# campainha.net
KiCad netlist of a schematic drawn in EAGLE
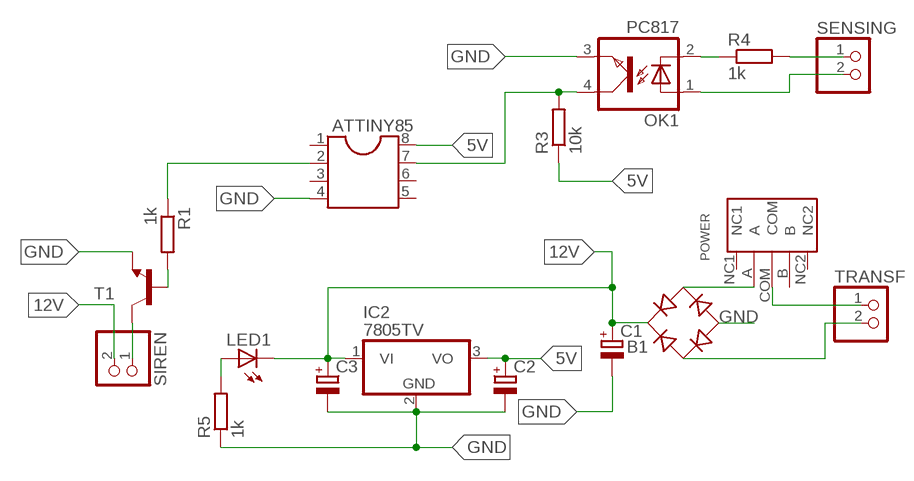
[diagram p0: schematic, sheet 1]

(export (version "E")
  (design (tool "Eeschema 10.0.6"))
  (components
    (comp (ref "ATTINY85")
      (value "DIL8S")
      (footprint "eagle-import:SOCKET-08")
      (libsource (lib "eagle-import") (part "DIL8S"))
    )
    (comp (ref "B1")
      (value "DBDB104G")
      (footprint "eagle-import:DB")
      (libsource (lib "eagle-import") (part "DB?GDB104"))
    )
    (comp (ref "C1")
      (value "CPOL-EUE2,5-6E")
      (footprint "eagle-import:E2,5-6E")
      (libsource (lib "eagle-import") (part "CPOL-EUE2,5-6E"))
    )
    (comp (ref "C2")
      (value "CPOL-EUE1.8-4")
      (footprint "eagle-import:E1,8-4")
      (libsource (lib "eagle-import") (part "CPOL-EUE1.8-4"))
    )
    (comp (ref "C3")
      (value "CPOL-EUE1.8-4")
      (footprint "eagle-import:E1,8-4")
      (libsource (lib "eagle-import") (part "CPOL-EUE1.8-4"))
    )
    (comp (ref "IC2")
      (value "7805TV")
      (footprint "eagle-import:TO220V")
      (libsource (lib "eagle-import") (part "78TV05"))
    )
    (comp (ref "LED1")
      (value "LED3MM")
      (footprint "eagle-import:LED3MM")
      (libsource (lib "eagle-import") (part "LED3MM"))
    )
    (comp (ref "OK1")
      (value "PC817")
      (footprint "eagle-import:DIL04")
      (fields (field (name "MPN") "PC817X4J000F"))
      (libsource (lib "eagle-import") (part "PC817"))
    )
    (comp (ref "POWER")
      (value "SWITCH-2H-3P-REINFORCE")
      (footprint "eagle-import:3P-2CH-2.0-8.8X4.4X4.7H-90D-REINFORCE")
      (libsource (lib "eagle-import") (part "SWITCH-2H-3P-REINFORCE"))
    )
    (comp (ref "R1")
      (value "1k")
      (footprint "eagle-import:0204_7")
      (libsource (lib "eagle-import") (part "R-EU_0204/7"))
    )
    (comp (ref "R3")
      (value "10k")
      (footprint "eagle-import:0204_7")
      (libsource (lib "eagle-import") (part "R-EU_0204/7"))
    )
    (comp (ref "R4")
      (value "1k")
      (footprint "eagle-import:0204_7")
      (libsource (lib "eagle-import") (part "R-EU_0204/7"))
    )
    (comp (ref "R5")
      (value "1k")
      (footprint "eagle-import:0204_7")
      (libsource (lib "eagle-import") (part "R-EU_0204/7"))
    )
    (comp (ref "SENSING")
      (value "PINHD-1X2")
      (footprint "eagle-import:1X02")
      (libsource (lib "eagle-import") (part "PINHD-1X2"))
    )
    (comp (ref "SIREN")
      (value "PINHD-1X2")
      (footprint "eagle-import:1X02")
      (libsource (lib "eagle-import") (part "PINHD-1X2"))
    )
    (comp (ref "T1")
      (value "TRANSISTOR_NPNTO92")
      (footprint "eagle-import:TO-92")
      (libsource (lib "eagle-import") (part "TRANSISTOR_NPNTO92"))
    )
    (comp (ref "TRANSF")
      (value "PINHD-1X2")
      (footprint "eagle-import:1X02")
      (libsource (lib "eagle-import") (part "PINHD-1X2"))
    )
  )
  (nets
    (net (code "1") (name "5V") (class "Default")
      (node (ref "ATTINY85") (pin "8") (pinfunction "8_8") (pintype "passive"))
      (node (ref "C2") (pin "+") (pinfunction "+_+") (pintype "passive"))
      (node (ref "IC2") (pin "3") (pinfunction "VO_3") (pintype "passive"))
      (node (ref "R3") (pin "1") (pinfunction "1_1") (pintype "passive"))
    )
    (net (code "2") (name "12V") (class "Default")
      (node (ref "B1") (pin "+") (pinfunction "+_+") (pintype "passive"))
      (node (ref "C1") (pin "+") (pinfunction "+_+") (pintype "passive"))
      (node (ref "C3") (pin "+") (pinfunction "+_+") (pintype "passive"))
      (node (ref "IC2") (pin "1") (pinfunction "VI_1") (pintype "input"))
      (node (ref "LED1") (pin "K") (pinfunction "C_K") (pintype "passive"))
      (node (ref "SIREN") (pin "2") (pinfunction "2_2") (pintype "passive"))
    )
    (net (code "3") (name "GND") (class "Default")
      (node (ref "ATTINY85") (pin "4") (pinfunction "4_4") (pintype "passive"))
      (node (ref "B1") (pin "-") (pinfunction "-_-") (pintype "passive"))
      (node (ref "C1") (pin "-") (pinfunction "-_-") (pintype "passive"))
      (node (ref "C2") (pin "-") (pinfunction "-_-") (pintype "passive"))
      (node (ref "C3") (pin "-") (pinfunction "-_-") (pintype "passive"))
      (node (ref "IC2") (pin "2") (pinfunction "GND_2") (pintype "passive"))
      (node (ref "OK1") (pin "3") (pinfunction "EMIT_3") (pintype "passive"))
      (node (ref "R5") (pin "1") (pinfunction "1_1") (pintype "passive"))
      (node (ref "T1") (pin "1") (pinfunction "E_1") (pintype "passive"))
    )
    (net (code "4") (name "Net-(ATTINY85-Pad2)") (class "Default")
      (node (ref "ATTINY85") (pin "2") (pinfunction "2_2") (pintype "passive"))
      (node (ref "R1") (pin "1") (pinfunction "1_1") (pintype "passive"))
    )
    (net (code "5") (name "Net-(B1-PadAC1)") (class "Default")
      (node (ref "B1") (pin "AC1") (pinfunction "AC1_AC1") (pintype "passive"))
      (node (ref "TRANSF") (pin "2") (pinfunction "2_2") (pintype "passive"))
    )
    (net (code "6") (name "Net-(B1-PadAC2)") (class "Default")
      (node (ref "B1") (pin "AC2") (pinfunction "AC2_AC2") (pintype "passive"))
      (node (ref "POWER") (pin "A") (pinfunction "A_A") (pintype "bidirectional"))
    )
    (net (code "7") (name "Net-(LED1-PadA)") (class "Default")
      (node (ref "LED1") (pin "A") (pinfunction "A_A") (pintype "passive"))
      (node (ref "R5") (pin "2") (pinfunction "2_2") (pintype "passive"))
    )
    (net (code "8") (name "Net-(OK1-A)") (class "Default")
      (node (ref "OK1") (pin "1") (pinfunction "A_1") (pintype "passive"))
      (node (ref "SENSING") (pin "2") (pinfunction "2_2") (pintype "passive"))
    )
    (net (code "9") (name "Net-(OK1-C)") (class "Default")
      (node (ref "OK1") (pin "2") (pinfunction "C_2") (pintype "passive"))
      (node (ref "R4") (pin "1") (pinfunction "1_1") (pintype "passive"))
    )
    (net (code "10") (name "Net-(OK1-COL)") (class "Default")
      (node (ref "ATTINY85") (pin "7") (pinfunction "7_7") (pintype "passive"))
      (node (ref "OK1") (pin "4") (pinfunction "COL_4") (pintype "passive"))
      (node (ref "R3") (pin "2") (pinfunction "2_2") (pintype "passive"))
    )
    (net (code "11") (name "Net-(POWER-PadCOM)") (class "Default")
      (node (ref "POWER") (pin "COM") (pinfunction "COM_COM") (pintype "bidirectional"))
      (node (ref "TRANSF") (pin "1") (pinfunction "1_1") (pintype "passive"))
    )
    (net (code "12") (name "Net-(R4-Pad2)") (class "Default")
      (node (ref "R4") (pin "2") (pinfunction "2_2") (pintype "passive"))
      (node (ref "SENSING") (pin "1") (pinfunction "1_1") (pintype "passive"))
    )
    (net (code "13") (name "Net-(T1-B)") (class "Default")
      (node (ref "R1") (pin "2") (pinfunction "2_2") (pintype "passive"))
      (node (ref "T1") (pin "2") (pinfunction "B_2") (pintype "passive"))
    )
    (net (code "14") (name "Net-(T1-C)") (class "Default")
      (node (ref "SIREN") (pin "1") (pinfunction "1_1") (pintype "passive"))
      (node (ref "T1") (pin "3") (pinfunction "C_3") (pintype "passive"))
    )
    (net (code "15") (name "unconnected-(ATTINY85-Pad1)") (class "Default")
      (node (ref "ATTINY85") (pin "1") (pinfunction "1_1") (pintype "passive"))
    )
    (net (code "16") (name "unconnected-(ATTINY85-Pad3)") (class "Default")
      (node (ref "ATTINY85") (pin "3") (pinfunction "3_3") (pintype "passive"))
    )
    (net (code "17") (name "unconnected-(ATTINY85-Pad5)") (class "Default")
      (node (ref "ATTINY85") (pin "5") (pinfunction "5_5") (pintype "passive"))
    )
    (net (code "18") (name "unconnected-(ATTINY85-Pad6)") (class "Default")
      (node (ref "ATTINY85") (pin "6") (pinfunction "6_6") (pintype "passive"))
    )
    (net (code "19") (name "unconnected-(POWER-PadB)") (class "Default")
      (node (ref "POWER") (pin "B") (pinfunction "B_B") (pintype "bidirectional"))
    )
    (net (code "20") (name "unconnected-(POWER-PadNC1)") (class "Default")
      (node (ref "POWER") (pin "NC1") (pinfunction "NC1_NC1") (pintype "bidirectional"))
    )
    (net (code "21") (name "unconnected-(POWER-PadNC2)") (class "Default")
      (node (ref "POWER") (pin "NC2") (pinfunction "NC2_NC2") (pintype "bidirectional"))
    )
  )
)
